# PedalBoardAnalogInputs.net
KiCad netlist of a schematic drawn in Altium Designer
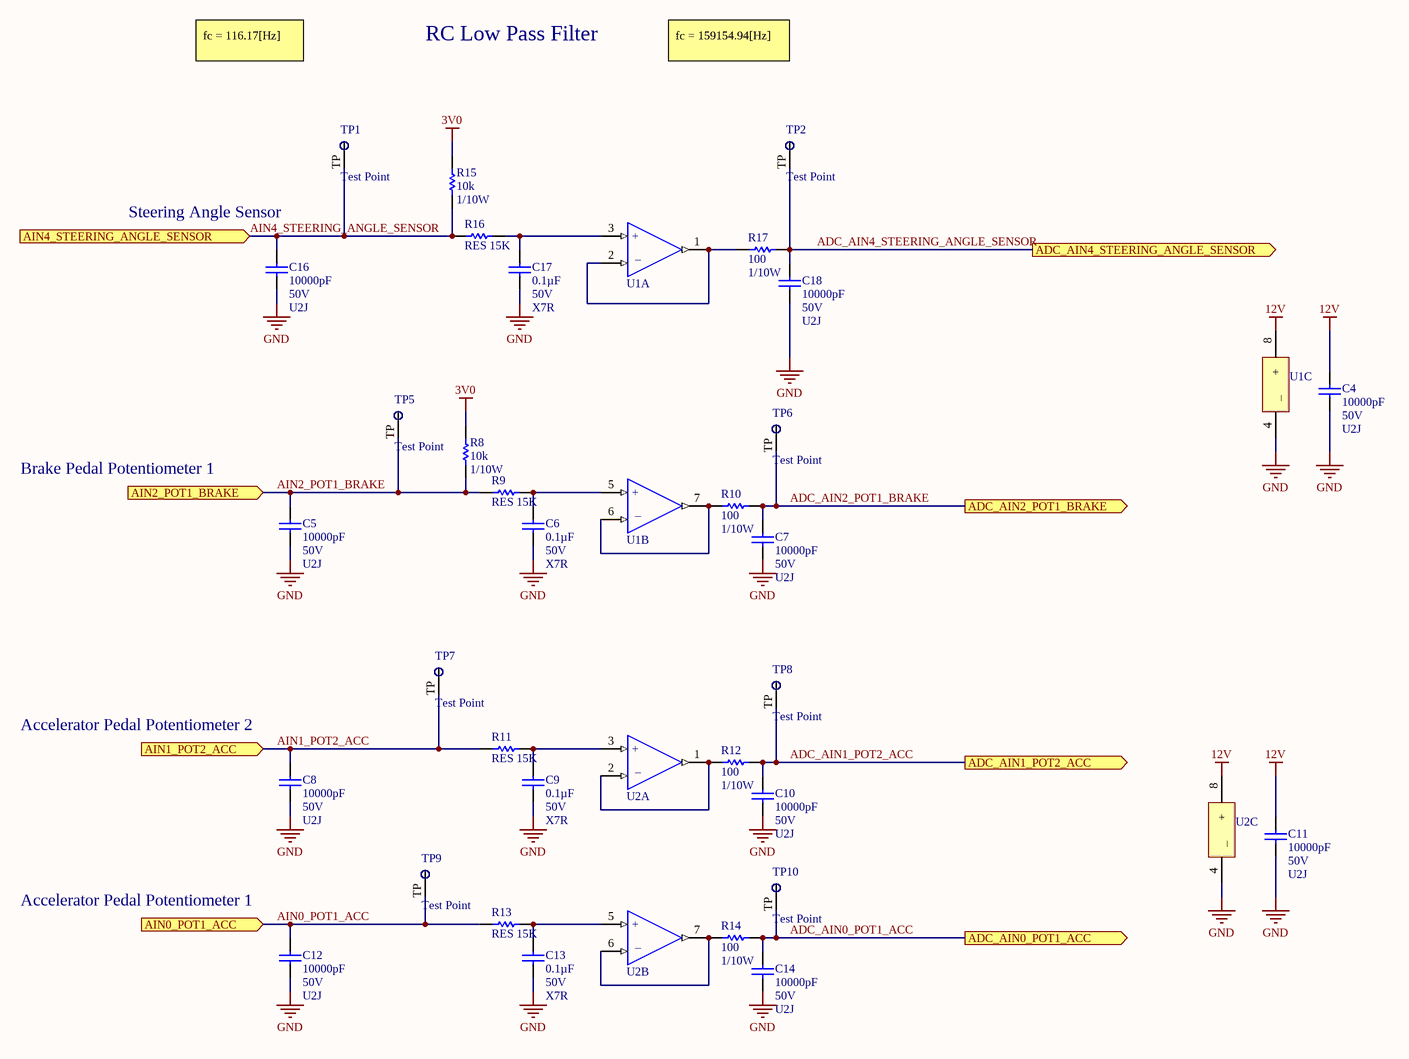
[diagram p0: PedalBoardAnalogInputs.SchDoc]

(export (version "E")
  (design (tool "Eeschema 10.0.6"))
  (components
    (comp (ref "C4")
      (value "CAP CER 10nF 50V 5% X7R 0603")
      (footprint "CAP, 0603")
      (description "10000pF ±5% 50V Ceramic Capacitor U2J 0603 (1608 Metric)")
      (fields
        (field (name "TOLERANCE") "±5%")
        (field (name "CAPACITANCE") "10000pF")
        (field (name "VOLTAGE") "50V")
        (field (name "TEMPERATURE COEFFICIENT") "U2J")
      )
      (libsource (lib "Schematic Diagrams") (part "CAP CER 10nF 50V 5% X7R 0603"))
    )
    (comp (ref "C5")
      (value "CAP CER 10nF 50V 5% X7R 0603")
      (footprint "CAP, 0603")
      (description "10000pF ±5% 50V Ceramic Capacitor U2J 0603 (1608 Metric)")
      (fields
        (field (name "TOLERANCE") "±5%")
        (field (name "CAPACITANCE") "10000pF")
        (field (name "VOLTAGE") "50V")
        (field (name "TEMPERATURE COEFFICIENT") "U2J")
      )
      (libsource (lib "Schematic Diagrams") (part "CAP CER 10nF 50V 5% X7R 0603"))
    )
    (comp (ref "C6")
      (value "CAP CER 0.1UF 50V 10% X7R 0603")
      (footprint "CAP, 0603")
      (description "0.10µF ±10% 50V Ceramic Capacitor X7R 0603 (1608 Metric)")
      (fields
        (field (name "TOLERANCE") "±10%")
        (field (name "CAPACITANCE") "0.1µF")
        (field (name "VOLTAGE") "50V")
        (field (name "TEMPERATURE COEFFICIENT") "X7R")
      )
      (libsource (lib "Schematic Diagrams") (part "CAP CER 0.1UF 50V 10% X7R 0603"))
    )
    (comp (ref "C7")
      (value "CAP CER 10nF 50V 5% X7R 0603")
      (footprint "CAP, 0603")
      (description "10000pF ±5% 50V Ceramic Capacitor U2J 0603 (1608 Metric)")
      (fields
        (field (name "TOLERANCE") "±5%")
        (field (name "CAPACITANCE") "10000pF")
        (field (name "VOLTAGE") "50V")
        (field (name "TEMPERATURE COEFFICIENT") "U2J")
      )
      (libsource (lib "Schematic Diagrams") (part "CAP CER 10nF 50V 5% X7R 0603"))
    )
    (comp (ref "C8")
      (value "CAP CER 10nF 50V 5% X7R 0603")
      (footprint "CAP, 0603")
      (description "10000pF ±5% 50V Ceramic Capacitor U2J 0603 (1608 Metric)")
      (fields
        (field (name "TOLERANCE") "±5%")
        (field (name "CAPACITANCE") "10000pF")
        (field (name "VOLTAGE") "50V")
        (field (name "TEMPERATURE COEFFICIENT") "U2J")
      )
      (libsource (lib "Schematic Diagrams") (part "CAP CER 10nF 50V 5% X7R 0603"))
    )
    (comp (ref "C9")
      (value "CAP CER 0.1UF 50V 10% X7R 0603")
      (footprint "CAP, 0603")
      (description "0.10µF ±10% 50V Ceramic Capacitor X7R 0603 (1608 Metric)")
      (fields
        (field (name "TOLERANCE") "±10%")
        (field (name "CAPACITANCE") "0.1µF")
        (field (name "VOLTAGE") "50V")
        (field (name "TEMPERATURE COEFFICIENT") "X7R")
      )
      (libsource (lib "Schematic Diagrams") (part "CAP CER 0.1UF 50V 10% X7R 0603"))
    )
    (comp (ref "C10")
      (value "CAP CER 10nF 50V 5% X7R 0603")
      (footprint "CAP, 0603")
      (description "10000pF ±5% 50V Ceramic Capacitor U2J 0603 (1608 Metric)")
      (fields
        (field (name "TOLERANCE") "±5%")
        (field (name "CAPACITANCE") "10000pF")
        (field (name "VOLTAGE") "50V")
        (field (name "TEMPERATURE COEFFICIENT") "U2J")
      )
      (libsource (lib "Schematic Diagrams") (part "CAP CER 10nF 50V 5% X7R 0603"))
    )
    (comp (ref "C11")
      (value "CAP CER 10nF 50V 5% X7R 0603")
      (footprint "CAP, 0603")
      (description "10000pF ±5% 50V Ceramic Capacitor U2J 0603 (1608 Metric)")
      (fields
        (field (name "TOLERANCE") "±5%")
        (field (name "CAPACITANCE") "10000pF")
        (field (name "VOLTAGE") "50V")
        (field (name "TEMPERATURE COEFFICIENT") "U2J")
      )
      (libsource (lib "Schematic Diagrams") (part "CAP CER 10nF 50V 5% X7R 0603"))
    )
    (comp (ref "C12")
      (value "CAP CER 10nF 50V 5% X7R 0603")
      (footprint "CAP, 0603")
      (description "10000pF ±5% 50V Ceramic Capacitor U2J 0603 (1608 Metric)")
      (fields
        (field (name "TOLERANCE") "±5%")
        (field (name "CAPACITANCE") "10000pF")
        (field (name "VOLTAGE") "50V")
        (field (name "TEMPERATURE COEFFICIENT") "U2J")
      )
      (libsource (lib "Schematic Diagrams") (part "CAP CER 10nF 50V 5% X7R 0603"))
    )
    (comp (ref "C13")
      (value "CAP CER 0.1UF 50V 10% X7R 0603")
      (footprint "CAP, 0603")
      (description "0.10µF ±10% 50V Ceramic Capacitor X7R 0603 (1608 Metric)")
      (fields
        (field (name "TOLERANCE") "±10%")
        (field (name "CAPACITANCE") "0.1µF")
        (field (name "VOLTAGE") "50V")
        (field (name "TEMPERATURE COEFFICIENT") "X7R")
      )
      (libsource (lib "Schematic Diagrams") (part "CAP CER 0.1UF 50V 10% X7R 0603"))
    )
    (comp (ref "C14")
      (value "CAP CER 10nF 50V 5% X7R 0603")
      (footprint "CAP, 0603")
      (description "10000pF ±5% 50V Ceramic Capacitor U2J 0603 (1608 Metric)")
      (fields
        (field (name "TOLERANCE") "±5%")
        (field (name "CAPACITANCE") "10000pF")
        (field (name "VOLTAGE") "50V")
        (field (name "TEMPERATURE COEFFICIENT") "U2J")
      )
      (libsource (lib "Schematic Diagrams") (part "CAP CER 10nF 50V 5% X7R 0603"))
    )
    (comp (ref "C16")
      (value "CAP CER 10nF 50V 5% X7R 0603")
      (footprint "CAP, 0603")
      (description "10000pF ±5% 50V Ceramic Capacitor U2J 0603 (1608 Metric)")
      (fields
        (field (name "TOLERANCE") "±5%")
        (field (name "CAPACITANCE") "10000pF")
        (field (name "VOLTAGE") "50V")
        (field (name "TEMPERATURE COEFFICIENT") "U2J")
      )
      (libsource (lib "Schematic Diagrams") (part "CAP CER 10nF 50V 5% X7R 0603"))
    )
    (comp (ref "C17")
      (value "CAP CER 0.1UF 50V 10% X7R 0603")
      (footprint "CAP, 0603")
      (description "0.10µF ±10% 50V Ceramic Capacitor X7R 0603 (1608 Metric)")
      (fields
        (field (name "TOLERANCE") "±10%")
        (field (name "CAPACITANCE") "0.1µF")
        (field (name "VOLTAGE") "50V")
        (field (name "TEMPERATURE COEFFICIENT") "X7R")
      )
      (libsource (lib "Schematic Diagrams") (part "CAP CER 0.1UF 50V 10% X7R 0603"))
    )
    (comp (ref "C18")
      (value "CAP CER 10nF 50V 5% X7R 0603")
      (footprint "CAP, 0603")
      (description "10000pF ±5% 50V Ceramic Capacitor U2J 0603 (1608 Metric)")
      (fields
        (field (name "TOLERANCE") "±5%")
        (field (name "CAPACITANCE") "10000pF")
        (field (name "VOLTAGE") "50V")
        (field (name "TEMPERATURE COEFFICIENT") "U2J")
      )
      (libsource (lib "Schematic Diagrams") (part "CAP CER 10nF 50V 5% X7R 0603"))
    )
    (comp (ref "R8")
      (value "RES 1K")
      (footprint "RES, 0603")
      (description "RES 10K")
      (fields
        (field (name "RESISTANCE") "10k")
        (field (name "TOLERANCE") "±1%")
        (field (name "POWER") "1/10W")
      )
      (libsource (lib "Schematic Diagrams") (part "RES 10K OHM 1% 1/10W 0603"))
    )
    (comp (ref "R9")
      (value "RES 15K")
      (footprint "RES, 0603")
      (description "15 kOhms ±1% 0.1W, 1/10W Chip Resistor 0603 (1608 Metric) Moisture Resistant Thick Film")
      (fields (field (name "TOLERANCE") "1%"))
      (libsource (lib "Schematic Diagrams") (part "RES SMD 15K OHM 1% 1/10W 0603"))
    )
    (comp (ref "R10")
      (value "RES 100 OHM 1% 1/10W 0603")
      (footprint "RES, 0603")
      (description "100 Ohm ±1% 0.1W, 1/10W Chip Resistor 0603 (1608 Metric) Moisture Resistant Thick Film")
      (fields
        (field (name "TOLERANCE") "±1%")
        (field (name "RESISTANCE") "100")
        (field (name "POWER") "1/10W")
      )
      (libsource (lib "Schematic Diagrams") (part "RES 100 OHM 1% 1/10W 0603"))
    )
    (comp (ref "R11")
      (value "RES 15K")
      (footprint "RES, 0603")
      (description "15 kOhms ±1% 0.1W, 1/10W Chip Resistor 0603 (1608 Metric) Moisture Resistant Thick Film")
      (fields (field (name "TOLERANCE") "1%"))
      (libsource (lib "Schematic Diagrams") (part "RES SMD 15K OHM 1% 1/10W 0603"))
    )
    (comp (ref "R12")
      (value "RES 100 OHM 1% 1/10W 0603")
      (footprint "RES, 0603")
      (description "100 Ohm ±1% 0.1W, 1/10W Chip Resistor 0603 (1608 Metric) Moisture Resistant Thick Film")
      (fields
        (field (name "TOLERANCE") "±1%")
        (field (name "RESISTANCE") "100")
        (field (name "POWER") "1/10W")
      )
      (libsource (lib "Schematic Diagrams") (part "RES 100 OHM 1% 1/10W 0603"))
    )
    (comp (ref "R13")
      (value "RES 15K")
      (footprint "RES, 0603")
      (description "15 kOhms ±1% 0.1W, 1/10W Chip Resistor 0603 (1608 Metric) Moisture Resistant Thick Film")
      (fields (field (name "TOLERANCE") "1%"))
      (libsource (lib "Schematic Diagrams") (part "RES SMD 15K OHM 1% 1/10W 0603"))
    )
    (comp (ref "R14")
      (value "RES 100 OHM 1% 1/10W 0603")
      (footprint "RES, 0603")
      (description "100 Ohm ±1% 0.1W, 1/10W Chip Resistor 0603 (1608 Metric) Moisture Resistant Thick Film")
      (fields
        (field (name "TOLERANCE") "±1%")
        (field (name "RESISTANCE") "100")
        (field (name "POWER") "1/10W")
      )
      (libsource (lib "Schematic Diagrams") (part "RES 100 OHM 1% 1/10W 0603"))
    )
    (comp (ref "R15")
      (value "RES 1K")
      (footprint "RES, 0603")
      (description "RES SMD 10K OHM 1% 1/10W 0603")
      (fields
        (field (name "RESISTANCE") "10k")
        (field (name "TOLERANCE") "±1%")
        (field (name "POWER") "1/10W")
      )
      (libsource (lib "Schematic Diagrams") (part "RES 10K OHM 1% 1/10W 0603"))
    )
    (comp (ref "R16")
      (value "RES 15K")
      (footprint "RES, 0603")
      (description "15 kOhms ±1% 0.1W, 1/10W Chip Resistor 0603 (1608 Metric) Moisture Resistant Thick Film")
      (fields (field (name "TOLERANCE") "1%"))
      (libsource (lib "Schematic Diagrams") (part "RES SMD 15K OHM 1% 1/10W 0603"))
    )
    (comp (ref "R17")
      (value "RES 100 OHM 1% 1/10W 0603")
      (footprint "RES, 0603")
      (description "100 Ohm ±1% 0.1W, 1/10W Chip Resistor 0603 (1608 Metric) Moisture Resistant Thick Film")
      (fields
        (field (name "TOLERANCE") "±1%")
        (field (name "RESISTANCE") "100")
        (field (name "POWER") "1/10W")
      )
      (libsource (lib "Schematic Diagrams") (part "RES 100 OHM 1% 1/10W 0603"))
    )
    (comp (ref "TP1")
      (value "Test Point")
      (footprint "Test Point")
      (libsource (lib "Schematic Diagrams") (part "Test Point"))
    )
    (comp (ref "TP2")
      (value "Test Point")
      (footprint "Test Point")
      (libsource (lib "Schematic Diagrams") (part "Test Point"))
    )
    (comp (ref "TP5")
      (value "Test Point")
      (footprint "Test Point")
      (libsource (lib "Schematic Diagrams") (part "Test Point"))
    )
    (comp (ref "TP6")
      (value "Test Point")
      (footprint "Test Point")
      (libsource (lib "Schematic Diagrams") (part "Test Point"))
    )
    (comp (ref "TP7")
      (value "Test Point")
      (footprint "Test Point")
      (libsource (lib "Schematic Diagrams") (part "Test Point"))
    )
    (comp (ref "TP8")
      (value "Test Point")
      (footprint "Test Point")
      (libsource (lib "Schematic Diagrams") (part "Test Point"))
    )
    (comp (ref "TP9")
      (value "Test Point")
      (footprint "Test Point")
      (libsource (lib "Schematic Diagrams") (part "Test Point"))
    )
    (comp (ref "TP10")
      (value "Test Point")
      (footprint "Test Point")
      (libsource (lib "Schematic Diagrams") (part "Test Point"))
    )
    (comp (ref "U1")
      (value "IC OP AMP DUAL GP RR 10MHZ 8-VSSOP")
      (footprint "IC OP AMP DUAL 8-VSSOP")
      (description "General Purpose Amplifier 2 Circuit Rail-to-Rail 8-VSSOP")
      (fields
        (field (name "MANUFACTURER") "Texas Instruments")
        (field (name "MANUFACTURER PART NUMBER") "OPA2197IDGKR")
      )
      (libsource (lib "Schematic Diagrams") (part "IC OP AMP DUAL GP RR 10MHZ 8-VSSOP"))
    )
    (comp (ref "U2")
      (value "IC OP AMP DUAL GP RR 10MHZ 8-VSSOP")
      (footprint "IC OP AMP DUAL 8-VSSOP")
      (description "General Purpose Amplifier 2 Circuit Rail-to-Rail 8-VSSOP")
      (fields
        (field (name "MANUFACTURER") "Texas Instruments")
        (field (name "MANUFACTURER PART NUMBER") "OPA2197IDGKR")
      )
      (libsource (lib "Schematic Diagrams") (part "IC OP AMP DUAL GP RR 10MHZ 8-VSSOP"))
    )
  )
  (nets
    (net (code "1") (name "/ADC_AIN0_POT1_ACC") (class "Default")
      (node (ref "C14") (pin "1") (pinfunction "1_1") (pintype "passive"))
      (node (ref "R14") (pin "1") (pinfunction "1_1") (pintype "passive"))
      (node (ref "TP10") (pin "TP") (pinfunction "1_TP") (pintype "passive"))
    )
    (net (code "2") (name "/ADC_AIN1_POT2_ACC") (class "Default")
      (node (ref "C10") (pin "1") (pinfunction "1_1") (pintype "passive"))
      (node (ref "R12") (pin "1") (pinfunction "1_1") (pintype "passive"))
      (node (ref "TP8") (pin "TP") (pinfunction "1_TP") (pintype "passive"))
    )
    (net (code "3") (name "/ADC_AIN2_POT1_BRAKE") (class "Default")
      (node (ref "C7") (pin "1") (pinfunction "1_1") (pintype "passive"))
      (node (ref "R10") (pin "1") (pinfunction "1_1") (pintype "passive"))
      (node (ref "TP6") (pin "TP") (pinfunction "1_TP") (pintype "passive"))
    )
    (net (code "4") (name "/ADC_AIN4_STEERING_ANGLE_SENSOR") (class "Default")
      (node (ref "C18") (pin "1") (pinfunction "1_1") (pintype "passive"))
      (node (ref "R17") (pin "1") (pinfunction "1_1") (pintype "passive"))
      (node (ref "TP2") (pin "TP") (pinfunction "1_TP") (pintype "passive"))
    )
    (net (code "5") (name "/AIN0_POT1_ACC") (class "Default")
      (node (ref "C12") (pin "1") (pinfunction "1_1") (pintype "passive"))
      (node (ref "R13") (pin "2") (pinfunction "2_2") (pintype "passive"))
      (node (ref "TP9") (pin "TP") (pinfunction "1_TP") (pintype "passive"))
    )
    (net (code "6") (name "/AIN1_POT2_ACC") (class "Default")
      (node (ref "C8") (pin "1") (pinfunction "1_1") (pintype "passive"))
      (node (ref "R11") (pin "2") (pinfunction "2_2") (pintype "passive"))
      (node (ref "TP7") (pin "TP") (pinfunction "1_TP") (pintype "passive"))
    )
    (net (code "7") (name "/AIN2_POT1_BRAKE") (class "Default")
      (node (ref "C5") (pin "1") (pinfunction "1_1") (pintype "passive"))
      (node (ref "R8") (pin "2") (pinfunction "2_2") (pintype "passive"))
      (node (ref "R9") (pin "2") (pinfunction "2_2") (pintype "passive"))
      (node (ref "TP5") (pin "TP") (pinfunction "1_TP") (pintype "passive"))
    )
    (net (code "8") (name "/AIN4_STEERING_ANGLE_SENSOR") (class "Default")
      (node (ref "C16") (pin "1") (pinfunction "1_1") (pintype "passive"))
      (node (ref "R15") (pin "2") (pinfunction "2_2") (pintype "passive"))
      (node (ref "R16") (pin "2") (pinfunction "2_2") (pintype "passive"))
      (node (ref "TP1") (pin "TP") (pinfunction "1_TP") (pintype "passive"))
    )
    (net (code "9") (name "3V0") (class "Default")
      (node (ref "R15") (pin "1") (pinfunction "1_1") (pintype "passive"))
      (node (ref "R8") (pin "1") (pinfunction "1_1") (pintype "passive"))
    )
    (net (code "10") (name "12V") (class "Default")
      (node (ref "C11") (pin "1") (pinfunction "1_1") (pintype "passive"))
      (node (ref "C4") (pin "1") (pinfunction "1_1") (pintype "passive"))
      (node (ref "U1") (pin "8") (pinfunction "+_8") (pintype "power_in"))
      (node (ref "U2") (pin "8") (pinfunction "+_8") (pintype "power_in"))
    )
    (net (code "11") (name "GND") (class "Default")
      (node (ref "C10") (pin "2") (pinfunction "2_2") (pintype "passive"))
      (node (ref "C11") (pin "2") (pinfunction "2_2") (pintype "passive"))
      (node (ref "C12") (pin "2") (pinfunction "2_2") (pintype "passive"))
      (node (ref "C13") (pin "2") (pinfunction "2_2") (pintype "passive"))
      (node (ref "C14") (pin "2") (pinfunction "2_2") (pintype "passive"))
      (node (ref "C16") (pin "2") (pinfunction "2_2") (pintype "passive"))
      (node (ref "C17") (pin "2") (pinfunction "2_2") (pintype "passive"))
      (node (ref "C18") (pin "2") (pinfunction "2_2") (pintype "passive"))
      (node (ref "C4") (pin "2") (pinfunction "2_2") (pintype "passive"))
      (node (ref "C5") (pin "2") (pinfunction "2_2") (pintype "passive"))
      (node (ref "C6") (pin "2") (pinfunction "2_2") (pintype "passive"))
      (node (ref "C7") (pin "2") (pinfunction "2_2") (pintype "passive"))
      (node (ref "C8") (pin "2") (pinfunction "2_2") (pintype "passive"))
      (node (ref "C9") (pin "2") (pinfunction "2_2") (pintype "passive"))
      (node (ref "U1") (pin "4") (pinfunction "__4") (pintype "power_in"))
      (node (ref "U2") (pin "4") (pinfunction "__4") (pintype "power_in"))
    )
    (net (code "12") (name "Net-(U1A-+IN_A)") (class "Default")
      (node (ref "C17") (pin "1") (pinfunction "1_1") (pintype "passive"))
      (node (ref "R16") (pin "1") (pinfunction "1_1") (pintype "passive"))
      (node (ref "U1") (pin "3") (pinfunction "+IN_A_3") (pintype "input"))
    )
    (net (code "13") (name "Net-(U1A--IN_A)") (class "Default")
      (node (ref "R17") (pin "2") (pinfunction "2_2") (pintype "passive"))
      (node (ref "U1") (pin "1") (pinfunction "OUT_A_1") (pintype "output"))
      (node (ref "U1") (pin "2") (pinfunction "-IN_A_2") (pintype "input"))
    )
    (net (code "14") (name "Net-(U1B-+IN_B)") (class "Default")
      (node (ref "C6") (pin "1") (pinfunction "1_1") (pintype "passive"))
      (node (ref "R9") (pin "1") (pinfunction "1_1") (pintype "passive"))
      (node (ref "U1") (pin "5") (pinfunction "+IN_B_5") (pintype "input"))
    )
    (net (code "15") (name "Net-(U1B--IN_B)") (class "Default")
      (node (ref "R10") (pin "2") (pinfunction "2_2") (pintype "passive"))
      (node (ref "U1") (pin "6") (pinfunction "-IN_B_6") (pintype "input"))
      (node (ref "U1") (pin "7") (pinfunction "OUT_B_7") (pintype "output"))
    )
    (net (code "16") (name "Net-(U2A-+IN_A)") (class "Default")
      (node (ref "C9") (pin "1") (pinfunction "1_1") (pintype "passive"))
      (node (ref "R11") (pin "1") (pinfunction "1_1") (pintype "passive"))
      (node (ref "U2") (pin "3") (pinfunction "+IN_A_3") (pintype "input"))
    )
    (net (code "17") (name "Net-(U2A--IN_A)") (class "Default")
      (node (ref "R12") (pin "2") (pinfunction "2_2") (pintype "passive"))
      (node (ref "U2") (pin "1") (pinfunction "OUT_A_1") (pintype "output"))
      (node (ref "U2") (pin "2") (pinfunction "-IN_A_2") (pintype "input"))
    )
    (net (code "18") (name "Net-(U2B-+IN_B)") (class "Default")
      (node (ref "C13") (pin "1") (pinfunction "1_1") (pintype "passive"))
      (node (ref "R13") (pin "1") (pinfunction "1_1") (pintype "passive"))
      (node (ref "U2") (pin "5") (pinfunction "+IN_B_5") (pintype "input"))
    )
    (net (code "19") (name "Net-(U2B--IN_B)") (class "Default")
      (node (ref "R14") (pin "2") (pinfunction "2_2") (pintype "passive"))
      (node (ref "U2") (pin "6") (pinfunction "-IN_B_6") (pintype "input"))
      (node (ref "U2") (pin "7") (pinfunction "OUT_B_7") (pintype "output"))
    )
  )
)
